# CONNECTEUR_4.net
KiCad netlist of a schematic drawn in Altium Designer
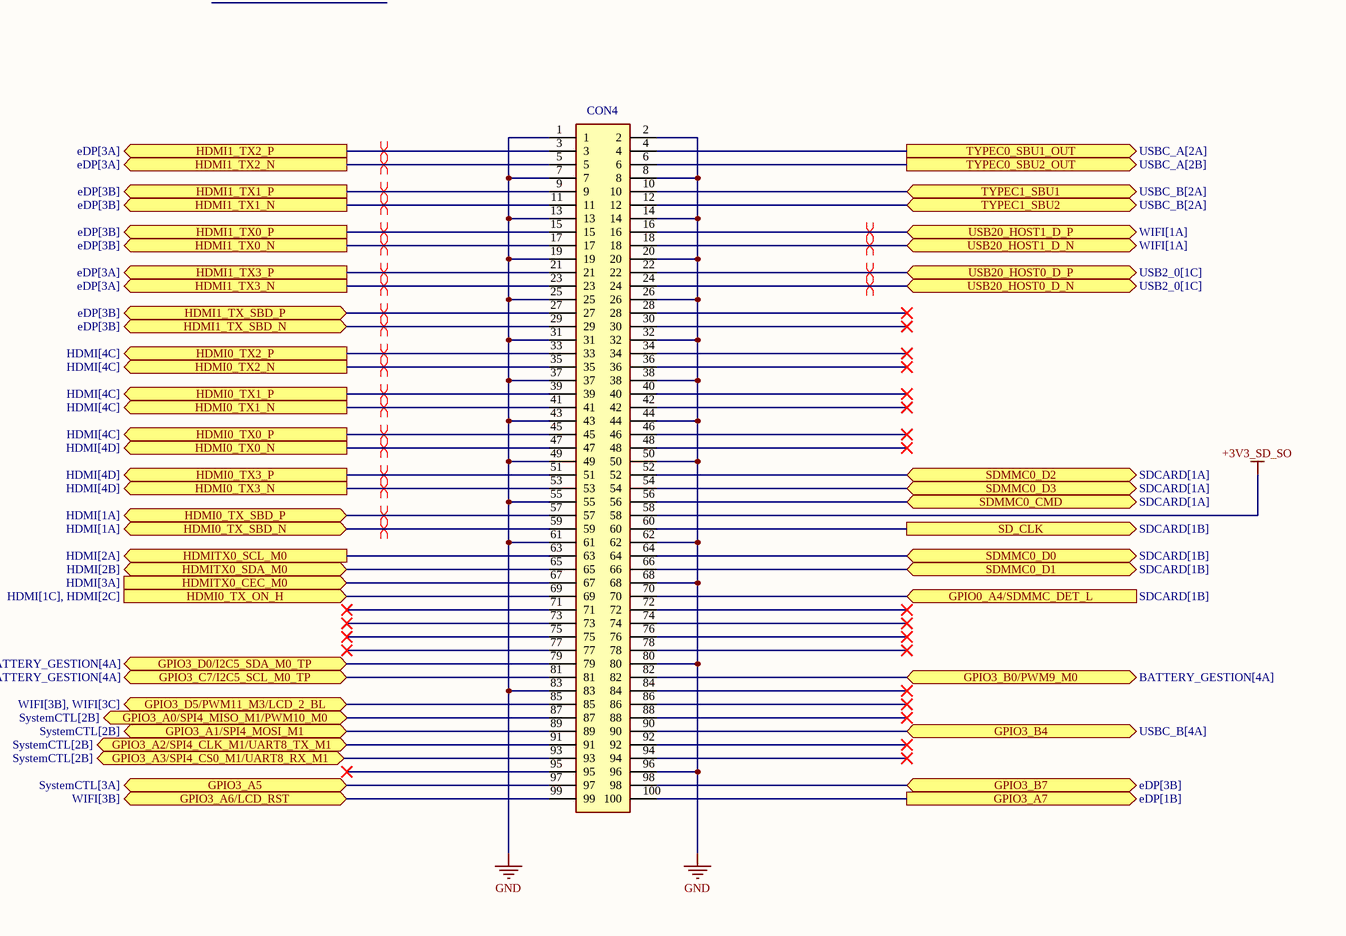
[diagram p0: CONNECTEUR_4.SchDoc, right]

(export (version "E")
  (design (tool "Eeschema 10.0.6"))
  (components
    (comp (ref "CON4")
      (value "DF40HC")
      (footprint "SamacSys:DF40HC30100DS04V51")
      (description "Stacking Board Connector, DF40 Series, Receptacle, 0.4 mm, 100, Surface Mount, G")
      (fields
        (field (name "MANUFACTURER_PART_NUMBER") "DF40HC(3.0)-100DS-0.4V(51")
        (field (name "MOUSER PART NUMBER") "798-DF40HC30100DS451")
      )
      (libsource (lib "SamacSys") (part "DF40HC(3.0)-100DS-0.4V(51)"))
    )
  )
  (nets
    (net (code "1") (name "+3V3_SD_SO") (class "Default")
      (node (ref "CON4") (pin "58") (pinfunction "58_58") (pintype "passive"))
    )
    (net (code "2") (name "/GPIO0_A4{slash}SDMMC_DET_L") (class "Default")
      (node (ref "CON4") (pin "70") (pinfunction "70_70") (pintype "passive"))
    )
    (net (code "3") (name "/GPIO3_A0{slash}SPI4_MISO_M1{slash}PWM10_M0") (class "Default")
      (node (ref "CON4") (pin "87") (pinfunction "87_87") (pintype "passive"))
    )
    (net (code "4") (name "/GPIO3_A1{slash}SPI4_MOSI_M1") (class "Default")
      (node (ref "CON4") (pin "89") (pinfunction "89_89") (pintype "passive"))
    )
    (net (code "5") (name "/GPIO3_A2{slash}SPI4_CLK_M1{slash}UART8_TX_M1") (class "Default")
      (node (ref "CON4") (pin "91") (pinfunction "91_91") (pintype "passive"))
    )
    (net (code "6") (name "/GPIO3_A3{slash}SPI4_CS0_M1{slash}UART8_RX_M1") (class "Default")
      (node (ref "CON4") (pin "93") (pinfunction "93_93") (pintype "passive"))
    )
    (net (code "7") (name "/GPIO3_A5") (class "Default")
      (node (ref "CON4") (pin "97") (pinfunction "97_97") (pintype "passive"))
    )
    (net (code "8") (name "/GPIO3_A6{slash}LCD_RST") (class "Default")
      (node (ref "CON4") (pin "99") (pinfunction "99_99") (pintype "passive"))
    )
    (net (code "9") (name "/GPIO3_A7") (class "Default")
      (node (ref "CON4") (pin "100") (pinfunction "100_100") (pintype "passive"))
    )
    (net (code "10") (name "/GPIO3_B0{slash}PWM9_M0") (class "Default")
      (node (ref "CON4") (pin "82") (pinfunction "82_82") (pintype "passive"))
    )
    (net (code "11") (name "/GPIO3_B4") (class "Default")
      (node (ref "CON4") (pin "90") (pinfunction "90_90") (pintype "passive"))
    )
    (net (code "12") (name "/GPIO3_B7") (class "Default")
      (node (ref "CON4") (pin "98") (pinfunction "98_98") (pintype "passive"))
    )
    (net (code "13") (name "/GPIO3_C7{slash}I2C5_SCL_M0_TP") (class "Default")
      (node (ref "CON4") (pin "81") (pinfunction "81_81") (pintype "passive"))
    )
    (net (code "14") (name "/GPIO3_D0{slash}I2C5_SDA_M0_TP") (class "Default")
      (node (ref "CON4") (pin "79") (pinfunction "79_79") (pintype "passive"))
    )
    (net (code "15") (name "/GPIO3_D5{slash}PWM11_M3{slash}LCD_2_BL") (class "Default")
      (node (ref "CON4") (pin "85") (pinfunction "85_85") (pintype "passive"))
    )
    (net (code "16") (name "/HDMI0_TX0_N") (class "Default")
      (node (ref "CON4") (pin "47") (pinfunction "47_47") (pintype "passive"))
    )
    (net (code "17") (name "/HDMI0_TX0_P") (class "Default")
      (node (ref "CON4") (pin "45") (pinfunction "45_45") (pintype "passive"))
    )
    (net (code "18") (name "/HDMI0_TX1_N") (class "Default")
      (node (ref "CON4") (pin "41") (pinfunction "41_41") (pintype "passive"))
    )
    (net (code "19") (name "/HDMI0_TX1_P") (class "Default")
      (node (ref "CON4") (pin "39") (pinfunction "39_39") (pintype "passive"))
    )
    (net (code "20") (name "/HDMI0_TX2_N") (class "Default")
      (node (ref "CON4") (pin "35") (pinfunction "35_35") (pintype "passive"))
    )
    (net (code "21") (name "/HDMI0_TX2_P") (class "Default")
      (node (ref "CON4") (pin "33") (pinfunction "33_33") (pintype "passive"))
    )
    (net (code "22") (name "/HDMI0_TX3_N") (class "Default")
      (node (ref "CON4") (pin "53") (pinfunction "53_53") (pintype "passive"))
    )
    (net (code "23") (name "/HDMI0_TX3_P") (class "Default")
      (node (ref "CON4") (pin "51") (pinfunction "51_51") (pintype "passive"))
    )
    (net (code "24") (name "/HDMI0_TX_ON_H") (class "Default")
      (node (ref "CON4") (pin "69") (pinfunction "69_69") (pintype "passive"))
    )
    (net (code "25") (name "/HDMI0_TX_SBD_N") (class "Default")
      (node (ref "CON4") (pin "59") (pinfunction "59_59") (pintype "passive"))
    )
    (net (code "26") (name "/HDMI0_TX_SBD_P") (class "Default")
      (node (ref "CON4") (pin "57") (pinfunction "57_57") (pintype "passive"))
    )
    (net (code "27") (name "/HDMI1_TX0_N") (class "Default")
      (node (ref "CON4") (pin "17") (pinfunction "17_17") (pintype "passive"))
    )
    (net (code "28") (name "/HDMI1_TX0_P") (class "Default")
      (node (ref "CON4") (pin "15") (pinfunction "15_15") (pintype "passive"))
    )
    (net (code "29") (name "/HDMI1_TX1_N") (class "Default")
      (node (ref "CON4") (pin "11") (pinfunction "11_11") (pintype "passive"))
    )
    (net (code "30") (name "/HDMI1_TX1_P") (class "Default")
      (node (ref "CON4") (pin "9") (pinfunction "9_9") (pintype "passive"))
    )
    (net (code "31") (name "/HDMI1_TX2_N") (class "Default")
      (node (ref "CON4") (pin "5") (pinfunction "5_5") (pintype "passive"))
    )
    (net (code "32") (name "/HDMI1_TX2_P") (class "Default")
      (node (ref "CON4") (pin "3") (pinfunction "3_3") (pintype "passive"))
    )
    (net (code "33") (name "/HDMI1_TX3_N") (class "Default")
      (node (ref "CON4") (pin "23") (pinfunction "23_23") (pintype "passive"))
    )
    (net (code "34") (name "/HDMI1_TX3_P") (class "Default")
      (node (ref "CON4") (pin "21") (pinfunction "21_21") (pintype "passive"))
    )
    (net (code "35") (name "/HDMI1_TX_SBD_N") (class "Default")
      (node (ref "CON4") (pin "29") (pinfunction "29_29") (pintype "passive"))
    )
    (net (code "36") (name "/HDMI1_TX_SBD_P") (class "Default")
      (node (ref "CON4") (pin "27") (pinfunction "27_27") (pintype "passive"))
    )
    (net (code "37") (name "/HDMITX0_CEC_M0") (class "Default")
      (node (ref "CON4") (pin "67") (pinfunction "67_67") (pintype "passive"))
    )
    (net (code "38") (name "/HDMITX0_SCL_M0") (class "Default")
      (node (ref "CON4") (pin "63") (pinfunction "63_63") (pintype "passive"))
    )
    (net (code "39") (name "/HDMITX0_SDA_M0") (class "Default")
      (node (ref "CON4") (pin "65") (pinfunction "65_65") (pintype "passive"))
    )
    (net (code "40") (name "/SDMMC0_CMD") (class "Default")
      (node (ref "CON4") (pin "56") (pinfunction "56_56") (pintype "passive"))
    )
    (net (code "41") (name "/SDMMC0_D0") (class "Default")
      (node (ref "CON4") (pin "64") (pinfunction "64_64") (pintype "passive"))
    )
    (net (code "42") (name "/SDMMC0_D1") (class "Default")
      (node (ref "CON4") (pin "66") (pinfunction "66_66") (pintype "passive"))
    )
    (net (code "43") (name "/SDMMC0_D2") (class "Default")
      (node (ref "CON4") (pin "52") (pinfunction "52_52") (pintype "passive"))
    )
    (net (code "44") (name "/SDMMC0_D3") (class "Default")
      (node (ref "CON4") (pin "54") (pinfunction "54_54") (pintype "passive"))
    )
    (net (code "45") (name "/SD_CLK") (class "Default")
      (node (ref "CON4") (pin "60") (pinfunction "60_60") (pintype "passive"))
    )
    (net (code "46") (name "/TYPEC0_SBU1_OUT") (class "Default")
      (node (ref "CON4") (pin "4") (pinfunction "4_4") (pintype "passive"))
    )
    (net (code "47") (name "/TYPEC0_SBU2_OUT") (class "Default")
      (node (ref "CON4") (pin "6") (pinfunction "6_6") (pintype "passive"))
    )
    (net (code "48") (name "/TYPEC1_SBU1") (class "Default")
      (node (ref "CON4") (pin "10") (pinfunction "10_10") (pintype "passive"))
    )
    (net (code "49") (name "/TYPEC1_SBU2") (class "Default")
      (node (ref "CON4") (pin "12") (pinfunction "12_12") (pintype "passive"))
    )
    (net (code "50") (name "/USB20_HOST0_D_N") (class "Default")
      (node (ref "CON4") (pin "24") (pinfunction "24_24") (pintype "passive"))
    )
    (net (code "51") (name "/USB20_HOST0_D_P") (class "Default")
      (node (ref "CON4") (pin "22") (pinfunction "22_22") (pintype "passive"))
    )
    (net (code "52") (name "/USB20_HOST1_D_N") (class "Default")
      (node (ref "CON4") (pin "18") (pinfunction "18_18") (pintype "passive"))
    )
    (net (code "53") (name "/USB20_HOST1_D_P") (class "Default")
      (node (ref "CON4") (pin "16") (pinfunction "16_16") (pintype "passive"))
    )
    (net (code "54") (name "GND") (class "Default")
      (node (ref "CON4") (pin "1") (pinfunction "1_1") (pintype "passive"))
      (node (ref "CON4") (pin "13") (pinfunction "13_13") (pintype "passive"))
      (node (ref "CON4") (pin "14") (pinfunction "14_14") (pintype "passive"))
      (node (ref "CON4") (pin "19") (pinfunction "19_19") (pintype "passive"))
      (node (ref "CON4") (pin "2") (pinfunction "2_2") (pintype "passive"))
      (node (ref "CON4") (pin "20") (pinfunction "20_20") (pintype "passive"))
      (node (ref "CON4") (pin "25") (pinfunction "25_25") (pintype "passive"))
      (node (ref "CON4") (pin "26") (pinfunction "26_26") (pintype "passive"))
      (node (ref "CON4") (pin "31") (pinfunction "31_31") (pintype "passive"))
      (node (ref "CON4") (pin "32") (pinfunction "32_32") (pintype "passive"))
      (node (ref "CON4") (pin "37") (pinfunction "37_37") (pintype "passive"))
      (node (ref "CON4") (pin "38") (pinfunction "38_38") (pintype "passive"))
      (node (ref "CON4") (pin "43") (pinfunction "43_43") (pintype "passive"))
      (node (ref "CON4") (pin "44") (pinfunction "44_44") (pintype "passive"))
      (node (ref "CON4") (pin "49") (pinfunction "49_49") (pintype "passive"))
      (node (ref "CON4") (pin "50") (pinfunction "50_50") (pintype "passive"))
      (node (ref "CON4") (pin "55") (pinfunction "55_55") (pintype "passive"))
      (node (ref "CON4") (pin "61") (pinfunction "61_61") (pintype "passive"))
      (node (ref "CON4") (pin "62") (pinfunction "62_62") (pintype "passive"))
      (node (ref "CON4") (pin "68") (pinfunction "68_68") (pintype "passive"))
      (node (ref "CON4") (pin "7") (pinfunction "7_7") (pintype "passive"))
      (node (ref "CON4") (pin "8") (pinfunction "8_8") (pintype "passive"))
      (node (ref "CON4") (pin "80") (pinfunction "80_80") (pintype "passive"))
      (node (ref "CON4") (pin "83") (pinfunction "83_83") (pintype "passive"))
      (node (ref "CON4") (pin "96") (pinfunction "96_96") (pintype "passive"))
    )
    (net (code "55") (name "unconnected-(CON4-Pad28)") (class "Default")
      (node (ref "CON4") (pin "28") (pinfunction "28_28") (pintype "passive+no_connect"))
    )
    (net (code "56") (name "unconnected-(CON4-Pad30)") (class "Default")
      (node (ref "CON4") (pin "30") (pinfunction "30_30") (pintype "passive+no_connect"))
    )
    (net (code "57") (name "unconnected-(CON4-Pad34)") (class "Default")
      (node (ref "CON4") (pin "34") (pinfunction "34_34") (pintype "passive+no_connect"))
    )
    (net (code "58") (name "unconnected-(CON4-Pad36)") (class "Default")
      (node (ref "CON4") (pin "36") (pinfunction "36_36") (pintype "passive+no_connect"))
    )
    (net (code "59") (name "unconnected-(CON4-Pad40)") (class "Default")
      (node (ref "CON4") (pin "40") (pinfunction "40_40") (pintype "passive+no_connect"))
    )
    (net (code "60") (name "unconnected-(CON4-Pad42)") (class "Default")
      (node (ref "CON4") (pin "42") (pinfunction "42_42") (pintype "passive+no_connect"))
    )
    (net (code "61") (name "unconnected-(CON4-Pad46)") (class "Default")
      (node (ref "CON4") (pin "46") (pinfunction "46_46") (pintype "passive+no_connect"))
    )
    (net (code "62") (name "unconnected-(CON4-Pad48)") (class "Default")
      (node (ref "CON4") (pin "48") (pinfunction "48_48") (pintype "passive+no_connect"))
    )
    (net (code "63") (name "unconnected-(CON4-Pad71)") (class "Default")
      (node (ref "CON4") (pin "71") (pinfunction "71_71") (pintype "passive+no_connect"))
    )
    (net (code "64") (name "unconnected-(CON4-Pad72)") (class "Default")
      (node (ref "CON4") (pin "72") (pinfunction "72_72") (pintype "passive+no_connect"))
    )
    (net (code "65") (name "unconnected-(CON4-Pad73)") (class "Default")
      (node (ref "CON4") (pin "73") (pinfunction "73_73") (pintype "passive+no_connect"))
    )
    (net (code "66") (name "unconnected-(CON4-Pad74)") (class "Default")
      (node (ref "CON4") (pin "74") (pinfunction "74_74") (pintype "passive+no_connect"))
    )
    (net (code "67") (name "unconnected-(CON4-Pad75)") (class "Default")
      (node (ref "CON4") (pin "75") (pinfunction "75_75") (pintype "passive+no_connect"))
    )
    (net (code "68") (name "unconnected-(CON4-Pad76)") (class "Default")
      (node (ref "CON4") (pin "76") (pinfunction "76_76") (pintype "passive+no_connect"))
    )
    (net (code "69") (name "unconnected-(CON4-Pad77)") (class "Default")
      (node (ref "CON4") (pin "77") (pinfunction "77_77") (pintype "passive+no_connect"))
    )
    (net (code "70") (name "unconnected-(CON4-Pad78)") (class "Default")
      (node (ref "CON4") (pin "78") (pinfunction "78_78") (pintype "passive+no_connect"))
    )
    (net (code "71") (name "unconnected-(CON4-Pad84)") (class "Default")
      (node (ref "CON4") (pin "84") (pinfunction "84_84") (pintype "passive+no_connect"))
    )
    (net (code "72") (name "unconnected-(CON4-Pad86)") (class "Default")
      (node (ref "CON4") (pin "86") (pinfunction "86_86") (pintype "passive+no_connect"))
    )
    (net (code "73") (name "unconnected-(CON4-Pad88)") (class "Default")
      (node (ref "CON4") (pin "88") (pinfunction "88_88") (pintype "passive+no_connect"))
    )
    (net (code "74") (name "unconnected-(CON4-Pad92)") (class "Default")
      (node (ref "CON4") (pin "92") (pinfunction "92_92") (pintype "passive+no_connect"))
    )
    (net (code "75") (name "unconnected-(CON4-Pad94)") (class "Default")
      (node (ref "CON4") (pin "94") (pinfunction "94_94") (pintype "passive+no_connect"))
    )
    (net (code "76") (name "unconnected-(CON4-Pad95)") (class "Default")
      (node (ref "CON4") (pin "95") (pinfunction "95_95") (pintype "passive+no_connect"))
    )
  )
)
